# MCU.net
KiCad netlist of a schematic drawn in Altium Designer
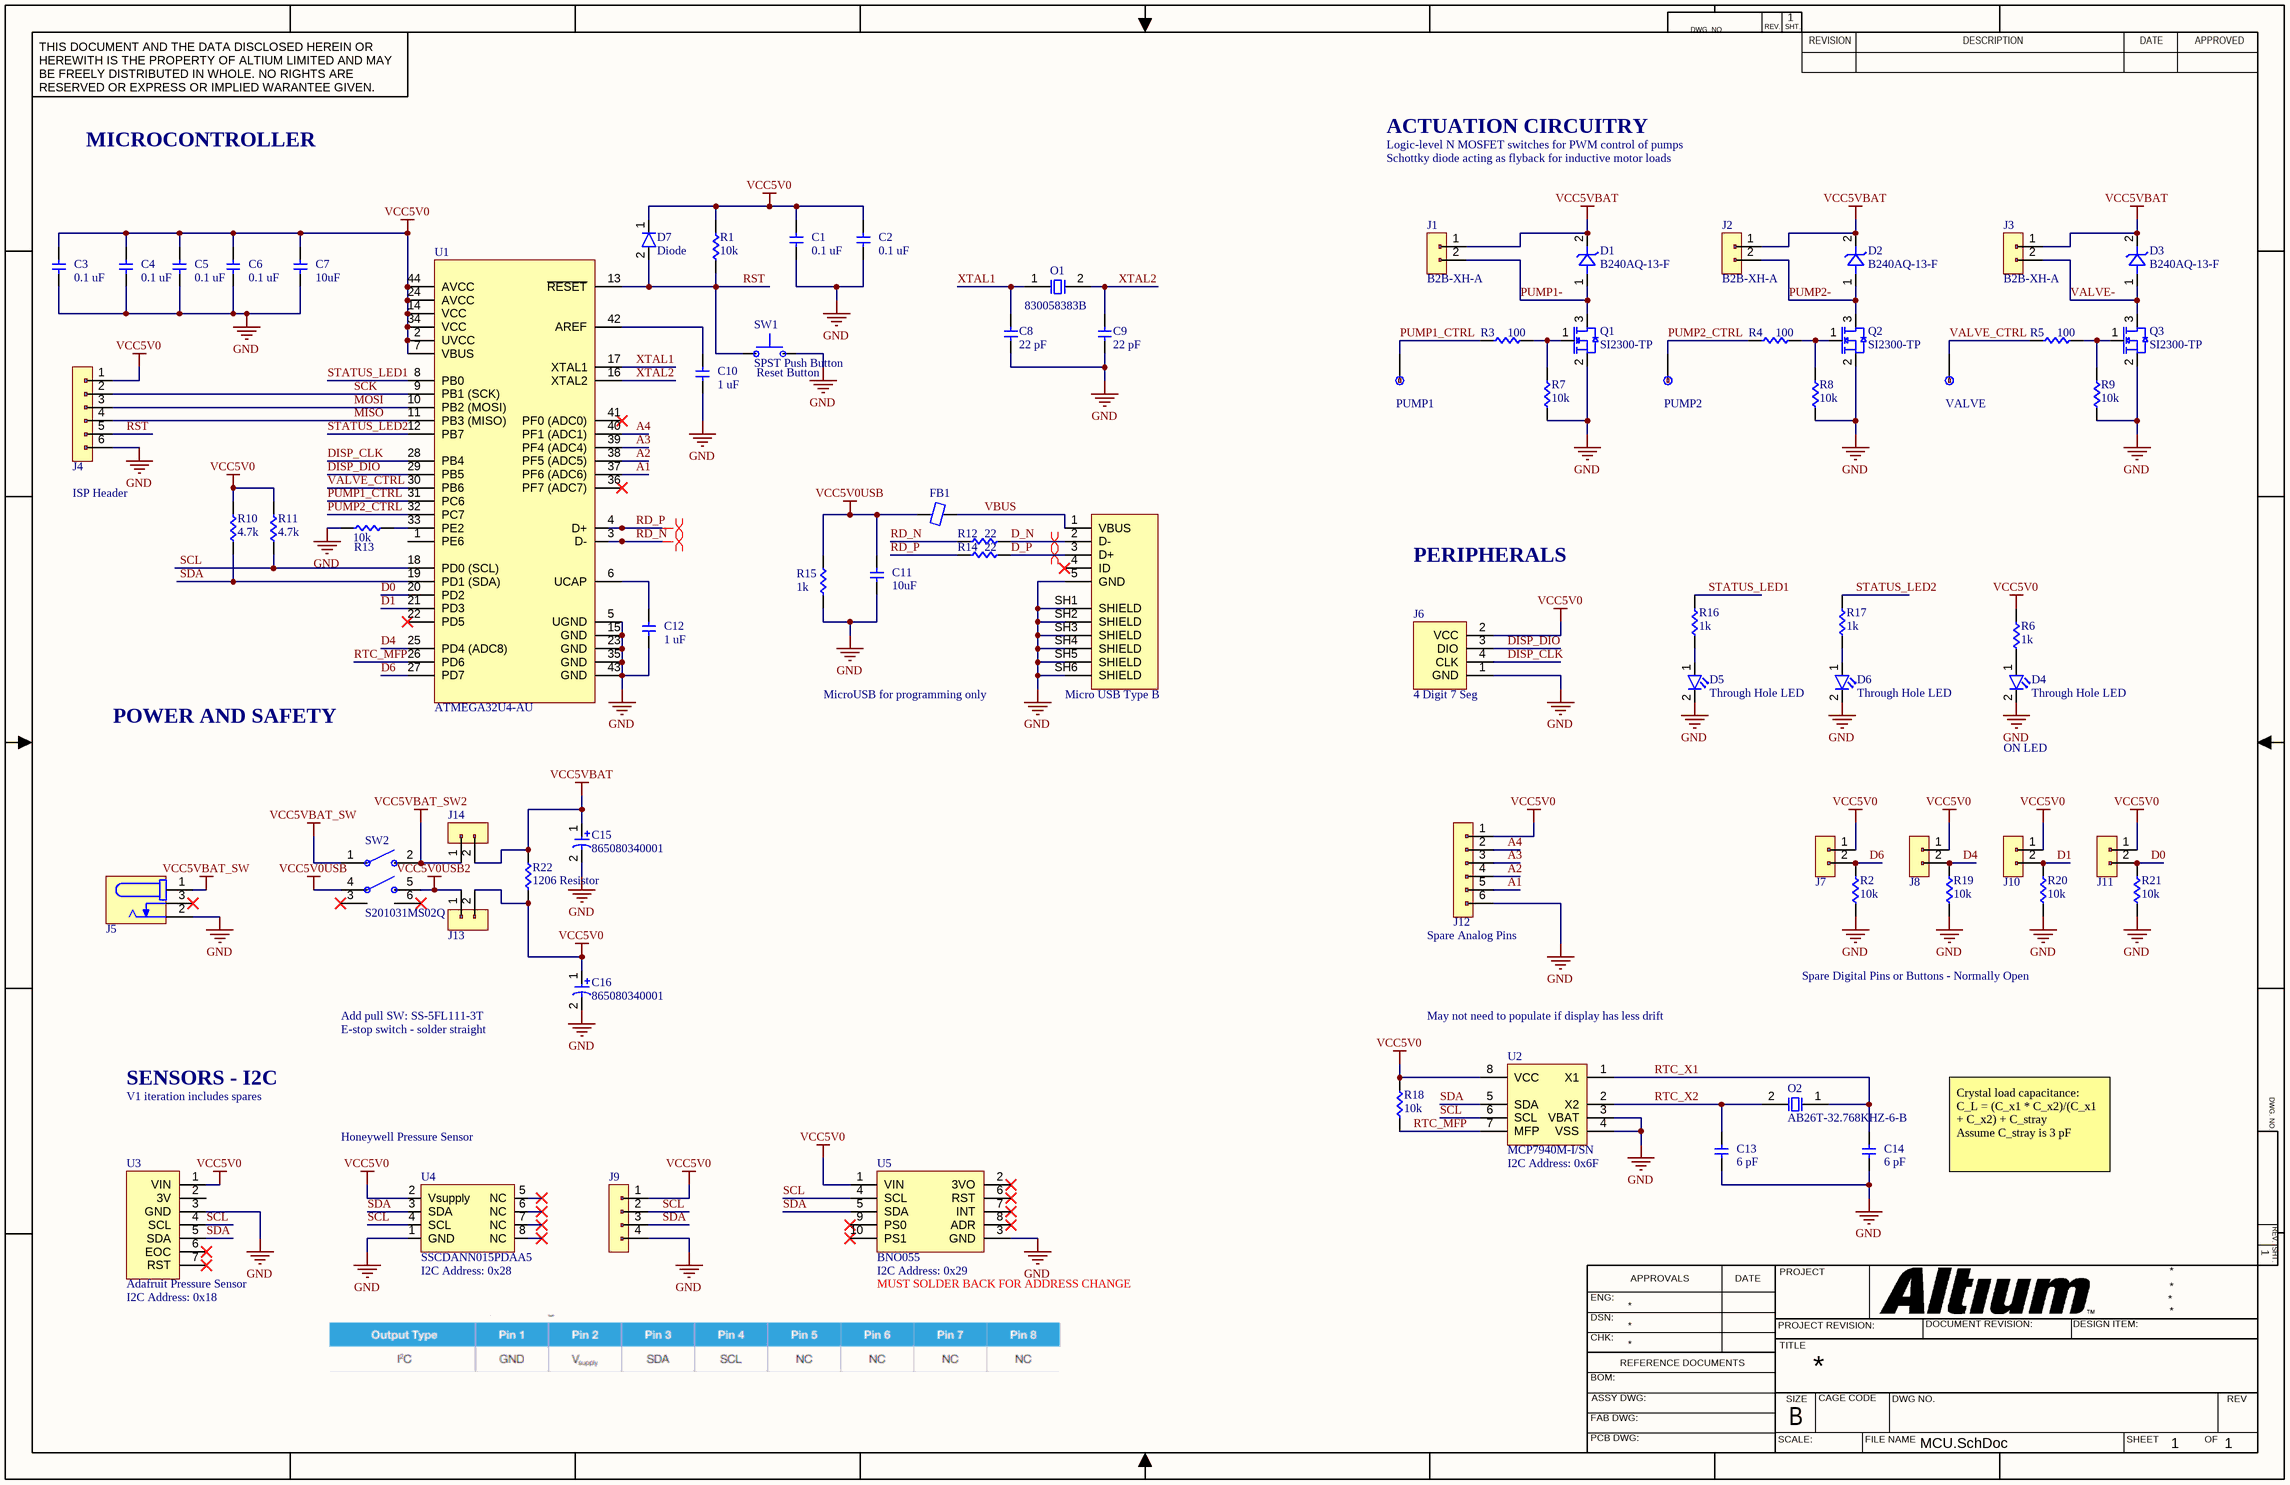
[diagram p0: MCU.SchDoc]

(export (version "E")
  (design (tool "Eeschema 10.0.6"))
  (components
    (comp (ref "*")
      (value "Micro USB Type B")
      (footprint "10118194-0001LF")
      (description "10118194-0001LF")
      (fields (field (name "MANUFACTURER") "Molex") (field (name "MANUFACTURER PART NUMBER") "105164-0001"))
      (libsource (lib "TourniquetPCBSch") (part "Micro USB Type B"))
    )
    (comp (ref "C1")
      (value "0.1 uF")
      (footprint "0603_CAP")
      (description "16V 100nF X7R ±10% 0603 Multilayer Ceramic Capacitors MLCC - SMD/SMT ROHS")
      (fields
        (field (name "MANUFACTURER") "Yageo Group")
        (field (name "MANUFACTURER PART NUMBER") "CC0603KRX7R7BB104")
      )
      (libsource (lib "TourniquetPCBSch") (part "CAPACITOR"))
    )
    (comp (ref "C2")
      (value "0.1 uF")
      (footprint "0603_CAP")
      (description "16V 100nF X7R ±10% 0603 Multilayer Ceramic Capacitors MLCC - SMD/SMT ROHS")
      (fields
        (field (name "MANUFACTURER") "Yageo Group")
        (field (name "MANUFACTURER PART NUMBER") "CC0603KRX7R7BB104")
      )
      (libsource (lib "TourniquetPCBSch") (part "CAPACITOR"))
    )
    (comp (ref "C3")
      (value "0.1 uF")
      (footprint "0603_CAP")
      (description "16V 100nF X7R ±10% 0603 Multilayer Ceramic Capacitors MLCC - SMD/SMT ROHS")
      (fields
        (field (name "MANUFACTURER") "Yageo Group")
        (field (name "MANUFACTURER PART NUMBER") "CC0603KRX7R7BB104")
      )
      (libsource (lib "TourniquetPCBSch") (part "CAPACITOR"))
    )
    (comp (ref "C4")
      (value "0.1 uF")
      (footprint "0603_CAP")
      (description "16V 100nF X7R ±10% 0603 Multilayer Ceramic Capacitors MLCC - SMD/SMT ROHS")
      (fields
        (field (name "MANUFACTURER") "Yageo Group")
        (field (name "MANUFACTURER PART NUMBER") "CC0603KRX7R7BB104")
      )
      (libsource (lib "TourniquetPCBSch") (part "CAPACITOR"))
    )
    (comp (ref "C5")
      (value "0.1 uF")
      (footprint "0603_CAP")
      (description "16V 100nF X7R ±10% 0603 Multilayer Ceramic Capacitors MLCC - SMD/SMT ROHS")
      (fields
        (field (name "MANUFACTURER") "Yageo Group")
        (field (name "MANUFACTURER PART NUMBER") "CC0603KRX7R7BB104")
      )
      (libsource (lib "TourniquetPCBSch") (part "CAPACITOR"))
    )
    (comp (ref "C6")
      (value "0.1 uF")
      (footprint "0603_CAP")
      (description "16V 100nF X7R ±10% 0603 Multilayer Ceramic Capacitors MLCC - SMD/SMT ROHS")
      (fields
        (field (name "MANUFACTURER") "Yageo Group")
        (field (name "MANUFACTURER PART NUMBER") "CC0603KRX7R7BB104")
      )
      (libsource (lib "TourniquetPCBSch") (part "CAPACITOR"))
    )
    (comp (ref "C7")
      (value "10uF")
      (footprint "0603_CAP")
      (description "16V 100nF X7R ±10% 0603 Multilayer Ceramic Capacitors MLCC - SMD/SMT ROHS")
      (fields
        (field (name "MANUFACTURER") "Yageo Group")
        (field (name "MANUFACTURER PART NUMBER") "CC0603KRX7R7BB104")
      )
      (libsource (lib "TourniquetPCBSch") (part "CAPACITOR"))
    )
    (comp (ref "C8")
      (value "22 pF")
      (footprint "0603_CAP")
      (description "16V 100nF X7R ±10% 0603 Multilayer Ceramic Capacitors MLCC - SMD/SMT ROHS")
      (fields
        (field (name "MANUFACTURER") "Yageo Group")
        (field (name "MANUFACTURER PART NUMBER") "CC0603KRX7R7BB104")
      )
      (libsource (lib "TourniquetPCBSch") (part "CAPACITOR"))
    )
    (comp (ref "C9")
      (value "22 pF")
      (footprint "0603_CAP")
      (description "16V 100nF X7R ±10% 0603 Multilayer Ceramic Capacitors MLCC - SMD/SMT ROHS")
      (fields
        (field (name "MANUFACTURER") "Yageo Group")
        (field (name "MANUFACTURER PART NUMBER") "CC0603KRX7R7BB104")
      )
      (libsource (lib "TourniquetPCBSch") (part "CAPACITOR"))
    )
    (comp (ref "C10")
      (value "1 uF")
      (footprint "0603_CAP")
      (description "16V 100nF X7R ±10% 0603 Multilayer Ceramic Capacitors MLCC - SMD/SMT ROHS")
      (fields
        (field (name "MANUFACTURER") "Yageo Group")
        (field (name "MANUFACTURER PART NUMBER") "CC0603KRX7R7BB104")
      )
      (libsource (lib "TourniquetPCBSch") (part "CAPACITOR"))
    )
    (comp (ref "C11")
      (value "10uF")
      (footprint "0603_CAP")
      (description "16V 100nF X7R ±10% 0603 Multilayer Ceramic Capacitors MLCC - SMD/SMT ROHS")
      (fields
        (field (name "MANUFACTURER") "Yageo Group")
        (field (name "MANUFACTURER PART NUMBER") "CC0603KRX7R7BB104")
      )
      (libsource (lib "TourniquetPCBSch") (part "CAPACITOR"))
    )
    (comp (ref "C12")
      (value "1 uF")
      (footprint "0603_CAP")
      (description "16V 100nF X7R ±10% 0603 Multilayer Ceramic Capacitors MLCC - SMD/SMT ROHS")
      (fields
        (field (name "MANUFACTURER") "Yageo Group")
        (field (name "MANUFACTURER PART NUMBER") "CC0603KRX7R7BB104")
      )
      (libsource (lib "TourniquetPCBSch") (part "CAPACITOR"))
    )
    (comp (ref "C13")
      (value "6 pF")
      (footprint "0603_CAP")
      (description "16V 100nF X7R ±10% 0603 Multilayer Ceramic Capacitors MLCC - SMD/SMT ROHS")
      (fields
        (field (name "MANUFACTURER") "Yageo Group")
        (field (name "MANUFACTURER PART NUMBER") "CC0603KRX7R7BB104")
      )
      (libsource (lib "TourniquetPCBSch") (part "CAPACITOR"))
    )
    (comp (ref "C14")
      (value "6 pF")
      (footprint "0603_CAP")
      (description "16V 100nF X7R ±10% 0603 Multilayer Ceramic Capacitors MLCC - SMD/SMT ROHS")
      (fields
        (field (name "MANUFACTURER") "Yageo Group")
        (field (name "MANUFACTURER PART NUMBER") "CC0603KRX7R7BB104")
      )
      (libsource (lib "TourniquetPCBSch") (part "CAPACITOR"))
    )
    (comp (ref "C15")
      (value "865080340001")
      (footprint "865080340001")
      (description "10 µF 16 V Aluminum Electrolytic Capacitors Radial, Can - SMD 2000 Hrs @ 105°C")
      (fields
        (field (name "MANUFACTURER") "Wurth")
        (field (name "MANUFACTURER PART NUMBER") "0878310641")
        (field (name "REVIEWED") "No")
      )
      (libsource (lib "TourniquetPCBSch") (part "CAP_POLARIZED"))
    )
    (comp (ref "C16")
      (value "865080340001")
      (footprint "865080340001")
      (description "10 µF 16 V Aluminum Electrolytic Capacitors Radial, Can - SMD 2000 Hrs @ 105°C")
      (fields
        (field (name "MANUFACTURER") "Wurth")
        (field (name "MANUFACTURER PART NUMBER") "0878310641")
        (field (name "REVIEWED") "No")
      )
      (libsource (lib "TourniquetPCBSch") (part "CAP_POLARIZED"))
    )
    (comp (ref "D1")
      (value "B240AQ-13-F")
      (footprint "SMA")
      (fields (field (name "MANUFACTURER") "Diodes Incorporated") (field (name "REVIEWED") "No"))
      (libsource (lib "TourniquetPCBSch") (part "SCHOTTKY"))
    )
    (comp (ref "D2")
      (value "B240AQ-13-F")
      (footprint "SMA")
      (fields (field (name "MANUFACTURER") "Diodes Incorporated") (field (name "REVIEWED") "No"))
      (libsource (lib "TourniquetPCBSch") (part "SCHOTTKY"))
    )
    (comp (ref "D3")
      (value "B240AQ-13-F")
      (footprint "SMA")
      (fields (field (name "MANUFACTURER") "Diodes Incorporated") (field (name "REVIEWED") "No"))
      (libsource (lib "TourniquetPCBSch") (part "SCHOTTKY"))
    )
    (comp (ref "D4")
      (value "Through Hole LED")
      (footprint "RED LED")
      (description "Red 645nm LED Indication - Discrete 2.1V Radial")
      (fields
        (field (name "MANUFACTURER") "Wurth Elektronik")
        (field (name "MANUFACTURER PART NUMBER") "151051RS11000")
      )
      (libsource (lib "TourniquetPCBSch") (part "LED RED DIFFUSED 5MM ROUND T/H"))
    )
    (comp (ref "D5")
      (value "Through Hole LED")
      (footprint "RED LED")
      (description "Red 645nm LED Indication - Discrete 2.1V Radial")
      (fields
        (field (name "MANUFACTURER") "Wurth Elektronik")
        (field (name "MANUFACTURER PART NUMBER") "151051RS11000")
      )
      (libsource (lib "TourniquetPCBSch") (part "LED RED DIFFUSED 5MM ROUND T/H"))
    )
    (comp (ref "D6")
      (value "Through Hole LED")
      (footprint "RED LED")
      (description "Red 645nm LED Indication - Discrete 2.1V Radial")
      (fields
        (field (name "MANUFACTURER") "Wurth Elektronik")
        (field (name "MANUFACTURER PART NUMBER") "151051RS11000")
      )
      (libsource (lib "TourniquetPCBSch") (part "LED RED DIFFUSED 5MM ROUND T/H"))
    )
    (comp (ref "D7")
      (value "Diode")
      (footprint "Diode")
      (description "Diode 100 V 150mA Surface Mount SOD-123")
      (fields (field (name "MANUFACTURER") "onsemi") (field (name "MANUFACTURER PART NUMBER") "1N4148WS"))
      (libsource (lib "TourniquetPCBSch") (part "Diode"))
    )
    (comp (ref "FB1")
      (value "Ferrite Bead 732-1591-2-ND")
      (footprint "Ferrite Bead")
      (description "30 Ohms @ 100 MHz 1 Signal Line Ferrite Bead 0603 (1608 Metric) 3A 40mOhm")
      (fields
        (field (name "MANUFACTURER") "KEMET")
        (field (name "MANUFACTURER PART NUMBER") "C0805F104K4RACTU")
      )
      (libsource (lib "TourniquetPCBSch") (part "Ferrite Bead 732-1591-2-ND"))
    )
    (comp (ref "J1")
      (value "B2B-XH-A")
      (footprint "B2B-XH")
      (description "Two Pin JST XH Header")
      (fields
        (field (name "MANUFACTURER") "Samtec")
        (field (name "MANUFACTURER PART NUMBER") "TSM-102-01-L-SV")
      )
      (libsource (lib "TourniquetPCBSch") (part "B2B-XH-A"))
    )
    (comp (ref "J2")
      (value "B2B-XH-A")
      (footprint "B2B-XH")
      (description "Two Pin JST XH Header")
      (fields
        (field (name "MANUFACTURER") "Samtec")
        (field (name "MANUFACTURER PART NUMBER") "TSM-102-01-L-SV")
      )
      (libsource (lib "TourniquetPCBSch") (part "B2B-XH-A"))
    )
    (comp (ref "J3")
      (value "B2B-XH-A")
      (footprint "B2B-XH")
      (description "Two Pin JST XH Header")
      (fields
        (field (name "MANUFACTURER") "Samtec")
        (field (name "MANUFACTURER PART NUMBER") "TSM-102-01-L-SV")
      )
      (libsource (lib "TourniquetPCBSch") (part "B2B-XH-A"))
    )
    (comp (ref "J4")
      (value "6PIN_HEADER")
      (footprint "6_pin_2.54mm")
      (fields
        (field (name "PART NUMBER") "0878310641")
        (field (name "MANUFACTURER") "Molex")
        (field (name "REVIEWED") "No")
      )
      (libsource (lib "TourniquetPCBSch") (part "6PIN_HEADER"))
    )
    (comp (ref "J5")
      (value "0878310641")
      (footprint "54-00166")
      (description "Barrel Jack")
      (fields (field (name "MANUFACTURER") "Molex") (field (name "REVIEWED") "No"))
      (libsource (lib "TourniquetPCBSch") (part "54-00166"))
    )
    (comp (ref "J6")
      (value "4 Digit 7 Seg")
      (footprint "B4B-XH")
      (fields
        (field (name "MANUFACTURER") "Sullins")
        (field (name "MANUFACTURER PART NUMBER") "NPTC041KFXC-RC")
      )
      (libsource (lib "TourniquetPCBSch") (part "4 Digit 7 Seg 1x4 Female Header"))
    )
    (comp (ref "J7")
      (value "0878310641")
      (footprint "2PIN_2.54mm")
      (description "2PIN")
      (fields (field (name "MANUFACTURER") "Molex") (field (name "REVIEWED") "No"))
      (libsource (lib "TourniquetPCBSch") (part "2PIN_HEADER"))
    )
    (comp (ref "J8")
      (value "0878310641")
      (footprint "2PIN_2.54mm")
      (description "2PIN")
      (fields (field (name "MANUFACTURER") "Molex") (field (name "REVIEWED") "No"))
      (libsource (lib "TourniquetPCBSch") (part "2PIN_HEADER"))
    )
    (comp (ref "J9")
      (value "4PIN_HEADER")
      (footprint "4PIN_2.54mm")
      (fields
        (field (name "PART NUMBER") "0878310641")
        (field (name "MANUFACTURER") "Molex")
        (field (name "REVIEWED") "No")
      )
      (libsource (lib "TourniquetPCBSch") (part "4PIN_HEADER"))
    )
    (comp (ref "J10")
      (value "0878310641")
      (footprint "2PIN_2.54mm")
      (description "2PIN")
      (fields (field (name "MANUFACTURER") "Molex") (field (name "REVIEWED") "No"))
      (libsource (lib "TourniquetPCBSch") (part "2PIN_HEADER"))
    )
    (comp (ref "J11")
      (value "0878310641")
      (footprint "2PIN_2.54mm")
      (description "2PIN")
      (fields (field (name "MANUFACTURER") "Molex") (field (name "REVIEWED") "No"))
      (libsource (lib "TourniquetPCBSch") (part "2PIN_HEADER"))
    )
    (comp (ref "J12")
      (value "6PIN_HEADER")
      (footprint "6_pin_2.54mm")
      (fields
        (field (name "PART NUMBER") "0878310641")
        (field (name "MANUFACTURER") "Molex")
        (field (name "REVIEWED") "No")
      )
      (libsource (lib "TourniquetPCBSch") (part "6PIN_HEADER"))
    )
    (comp (ref "J13")
      (value "0878310641")
      (footprint "2PIN_2.54mm")
      (description "2PIN")
      (fields (field (name "MANUFACTURER") "Molex") (field (name "REVIEWED") "No"))
      (libsource (lib "") (part "2PIN_HEADER_1"))
    )
    (comp (ref "J14")
      (value "0878310641")
      (footprint "2PIN_2.54mm")
      (description "2PIN")
      (fields (field (name "MANUFACTURER") "Molex") (field (name "REVIEWED") "No"))
      (libsource (lib "") (part "2PIN_HEADER_2"))
    )
    (comp (ref "O1")
      (value "830058383B")
      (footprint "830058383B")
      (description "16 MHz ±30ppm Crystal 20pF 40 Ohms HC-49/US")
      (fields
        (field (name "MANUFACTURER") "Epson")
        (field (name "MANUFACTURER PART NUMBER") "TSX-3225 16.0000MF18X-AC0")
      )
      (libsource (lib "TourniquetPCBSch") (part "830058383B"))
    )
    (comp (ref "O2")
      (value "AB26T-32.768KHZ-6-B")
      (footprint "XTAL_AB26T-32.768KHZ-6-B")
      (description "32.768 kHz ±20ppm Crystal 6pF 35 kOhms Cylindrical Can, Radial")
      (fields
        (field (name "MANUFACTURER") "Epson")
        (field (name "MANUFACTURER PART NUMBER") "TSX-3225 16.0000MF18X-AC0")
      )
      (libsource (lib "TourniquetPCBSch") (part "AB26T-32.768KHZ-6-B"))
    )
    (comp (ref "PUMP1")
      (value "1PIN_HEADER_TEST")
      (footprint "1PIN_2.54mm")
      (description "Test Point Hole")
      (fields
        (field (name "MANUFACTURER") "Molex")
        (field (name "MANUFACTURER PART NUMBER") "0878310641")
        (field (name "REVIEWED") "No")
      )
      (libsource (lib "TourniquetPCBSch") (part "1PIN_HEADER_TEST"))
    )
    (comp (ref "PUMP2")
      (value "1PIN_HEADER_TEST")
      (footprint "1PIN_2.54mm")
      (description "Test Point Hole")
      (fields
        (field (name "MANUFACTURER") "Molex")
        (field (name "MANUFACTURER PART NUMBER") "0878310641")
        (field (name "REVIEWED") "No")
      )
      (libsource (lib "TourniquetPCBSch") (part "1PIN_HEADER_TEST"))
    )
    (comp (ref "Q1")
      (value "SI2300-TP")
      (footprint "SOT23")
      (fields
        (field (name "MANUFACTURER") "MCC (Micro Commercial Components)")
        (field (name "REVIEWED") "No")
      )
      (libsource (lib "TourniquetPCBSch") (part "MOSFET_NCHANNEL"))
    )
    (comp (ref "Q2")
      (value "SI2300-TP")
      (footprint "SOT23")
      (fields
        (field (name "MANUFACTURER") "MCC (Micro Commercial Components)")
        (field (name "REVIEWED") "No")
      )
      (libsource (lib "TourniquetPCBSch") (part "MOSFET_NCHANNEL"))
    )
    (comp (ref "Q3")
      (value "SI2300-TP")
      (footprint "SOT23")
      (fields
        (field (name "MANUFACTURER") "MCC (Micro Commercial Components)")
        (field (name "REVIEWED") "No")
      )
      (libsource (lib "TourniquetPCBSch") (part "MOSFET_NCHANNEL"))
    )
    (comp (ref "R1")
      (value "10k")
      (footprint "0603_RES")
      (fields (field (name "TOLERANCE") "1%"))
      (libsource (lib "TourniquetPCBSch") (part "RESISTOR"))
    )
    (comp (ref "R2")
      (value "10k")
      (footprint "0603_RES")
      (fields (field (name "TOLERANCE") "1%"))
      (libsource (lib "TourniquetPCBSch") (part "RESISTOR"))
    )
    (comp (ref "R3")
      (value "100")
      (footprint "0603_RES")
      (fields (field (name "TOLERANCE") "1%"))
      (libsource (lib "TourniquetPCBSch") (part "RESISTOR"))
    )
    (comp (ref "R4")
      (value "100")
      (footprint "0603_RES")
      (fields (field (name "TOLERANCE") "1%"))
      (libsource (lib "TourniquetPCBSch") (part "RESISTOR"))
    )
    (comp (ref "R5")
      (value "100")
      (footprint "0603_RES")
      (fields (field (name "TOLERANCE") "1%"))
      (libsource (lib "TourniquetPCBSch") (part "RESISTOR"))
    )
    (comp (ref "R6")
      (value "1k")
      (footprint "0603_RES")
      (fields (field (name "TOLERANCE") "1%"))
      (libsource (lib "TourniquetPCBSch") (part "RESISTOR"))
    )
    (comp (ref "R7")
      (value "10k")
      (footprint "0603_RES")
      (fields (field (name "TOLERANCE") "1%"))
      (libsource (lib "TourniquetPCBSch") (part "RESISTOR"))
    )
    (comp (ref "R8")
      (value "10k")
      (footprint "0603_RES")
      (fields (field (name "TOLERANCE") "1%"))
      (libsource (lib "TourniquetPCBSch") (part "RESISTOR"))
    )
    (comp (ref "R9")
      (value "10k")
      (footprint "0603_RES")
      (fields (field (name "TOLERANCE") "1%"))
      (libsource (lib "TourniquetPCBSch") (part "RESISTOR"))
    )
    (comp (ref "R10")
      (value "4.7k")
      (footprint "0603_RES")
      (fields (field (name "TOLERANCE") "1%"))
      (libsource (lib "TourniquetPCBSch") (part "RESISTOR"))
    )
    (comp (ref "R11")
      (value "4.7k")
      (footprint "0603_RES")
      (fields (field (name "TOLERANCE") "1%"))
      (libsource (lib "TourniquetPCBSch") (part "RESISTOR"))
    )
    (comp (ref "R12")
      (value "22")
      (footprint "0603_RES")
      (fields (field (name "TOLERANCE") "1%"))
      (libsource (lib "TourniquetPCBSch") (part "RESISTOR"))
    )
    (comp (ref "R13")
      (value "10k")
      (footprint "0603_RES")
      (fields (field (name "TOLERANCE") "1%"))
      (libsource (lib "TourniquetPCBSch") (part "RESISTOR"))
    )
    (comp (ref "R14")
      (value "22")
      (footprint "0603_RES")
      (fields (field (name "TOLERANCE") "1%"))
      (libsource (lib "TourniquetPCBSch") (part "RESISTOR"))
    )
    (comp (ref "R15")
      (value "1k")
      (footprint "0603_RES")
      (fields (field (name "TOLERANCE") "1%"))
      (libsource (lib "TourniquetPCBSch") (part "RESISTOR"))
    )
    (comp (ref "R16")
      (value "1k")
      (footprint "0603_RES")
      (fields (field (name "TOLERANCE") "1%"))
      (libsource (lib "TourniquetPCBSch") (part "RESISTOR"))
    )
    (comp (ref "R17")
      (value "1k")
      (footprint "0603_RES")
      (fields (field (name "TOLERANCE") "1%"))
      (libsource (lib "TourniquetPCBSch") (part "RESISTOR"))
    )
    (comp (ref "R18")
      (value "10k")
      (footprint "0603_RES")
      (fields (field (name "TOLERANCE") "1%"))
      (libsource (lib "TourniquetPCBSch") (part "RESISTOR"))
    )
    (comp (ref "R19")
      (value "10k")
      (footprint "0603_RES")
      (fields (field (name "TOLERANCE") "1%"))
      (libsource (lib "TourniquetPCBSch") (part "RESISTOR"))
    )
    (comp (ref "R20")
      (value "10k")
      (footprint "0603_RES")
      (fields (field (name "TOLERANCE") "1%"))
      (libsource (lib "TourniquetPCBSch") (part "RESISTOR"))
    )
    (comp (ref "R21")
      (value "10k")
      (footprint "0603_RES")
      (fields (field (name "TOLERANCE") "1%"))
      (libsource (lib "TourniquetPCBSch") (part "RESISTOR"))
    )
    (comp (ref "R22")
      (value "1206 Resistor")
      (footprint "1206 Resistor")
      (libsource (lib "TourniquetPCBSch") (part "1206 Resistor"))
    )
    (comp (ref "SW1")
      (value "SPST Push Button")
      (footprint "Push Button")
      (description "Switch Tactile N.O. SPST Round Button Gull Wing 0.05A 12VDC 1.5N SMD Embossed T/R")
      (fields (field (name "MANUFACTURER") "Omron") (field (name "MANUFACTURER PART NUMBER") "B3U-1100PM"))
      (libsource (lib "TourniquetPCBSch") (part "SPST Push Button"))
    )
    (comp (ref "SW2")
      (value "S201031MS02Q")
      (footprint "DPST Sliding Switch")
      (libsource (lib "TourniquetPCBSch") (part "DPST Switch"))
    )
    (comp (ref "U1")
      (value "ATMEGA32U4-AU")
      (footprint "ATMEGA32U4-AU")
      (description "Microcontroller, Usb Controller 16/32K Of Isp Flash, TQFP44 Industrial, 8-BIT")
      (fields (field (name "MANUFACTURER") "Microchip"))
      (libsource (lib "TourniquetPCBSch") (part "ATMEGA32U4-AU"))
    )
    (comp (ref "U2")
      (value "MCP7940M-I/SN")
      (footprint "8SOIC")
      (description "RTC Clock")
      (fields
        (field (name "PART NUMBER") "0878310641")
        (field (name "MANUFACTURER") "Molex")
        (field (name "REVIEWED") "No")
      )
      (libsource (lib "TourniquetPCBSch") (part "MCP7940M"))
    )
    (comp (ref "U3")
      (value "Adafruit Pressure Sensor")
      (footprint "Adafruit Pressure Sensor")
      (description "Adafruit MPRLS Ported Pressure Sensor")
      (fields
        (field (name "MANUFACTURER") "Wurth Elektronik")
        (field (name "MANUFACTURER PART NUMBER") "61300711121")
      )
      (libsource (lib "TourniquetPCBSch") (part "Adafruit MPRLS Ported Pressure Sensor"))
    )
    (comp (ref "U4")
      (value "SSCDANN015PDAA5")
      (footprint "SSCDANN015PDAA5")
      (fields
        (field (name "MANUFACTURER") "Sullins")
        (field (name "MANUFACTURER PART NUMBER") "NPTC041KFXC-RC")
      )
      (libsource (lib "TourniquetPCBSch") (part "SSCDANN015PDAA5"))
    )
    (comp (ref "U5")
      (value "BNO055")
      (footprint "BNO055")
      (description "IMU")
      (fields
        (field (name "MANUFACTURER") "Adafruit")
        (field (name "MANUFACTURER PART NUMBER") "0878310641")
        (field (name "REVIEWED") "No")
      )
      (libsource (lib "TourniquetPCBSch") (part "BNO055"))
    )
    (comp (ref "VALVE")
      (value "1PIN_HEADER_TEST")
      (footprint "1PIN_2.54mm")
      (description "Test Point Hole")
      (fields
        (field (name "MANUFACTURER") "Molex")
        (field (name "MANUFACTURER PART NUMBER") "0878310641")
        (field (name "REVIEWED") "No")
      )
      (libsource (lib "TourniquetPCBSch") (part "1PIN_HEADER_TEST"))
    )
  )
  (nets
    (net (code "1") (name "/A1") (class "Default")
      (node (ref "J12") (pin "5") (pintype "passive"))
      (node (ref "U1") (pin "37") (pinfunction "PF6_(ADC6)_37") (pintype "passive"))
    )
    (net (code "2") (name "/A2") (class "Default")
      (node (ref "J12") (pin "4") (pintype "passive"))
      (node (ref "U1") (pin "38") (pinfunction "PF5_(ADC5)_38") (pintype "passive"))
    )
    (net (code "3") (name "/A3") (class "Default")
      (node (ref "J12") (pin "3") (pintype "passive"))
      (node (ref "U1") (pin "39") (pinfunction "PF4_(ADC4)_39") (pintype "passive"))
    )
    (net (code "4") (name "/A4") (class "Default")
      (node (ref "J12") (pin "2") (pintype "passive"))
      (node (ref "U1") (pin "40") (pinfunction "PF1_(ADC1)_40") (pintype "passive"))
    )
    (net (code "5") (name "/D0") (class "Default")
      (node (ref "J11") (pin "2") (pintype "passive"))
      (node (ref "R21") (pin "1") (pinfunction "1_1") (pintype "passive"))
      (node (ref "U1") (pin "20") (pinfunction "PD2_20") (pintype "passive"))
    )
    (net (code "6") (name "/D1") (class "Default")
      (node (ref "J10") (pin "2") (pintype "passive"))
      (node (ref "R20") (pin "1") (pinfunction "1_1") (pintype "passive"))
      (node (ref "U1") (pin "21") (pinfunction "PD3_21") (pintype "passive"))
    )
    (net (code "7") (name "/D4") (class "Default")
      (node (ref "J8") (pin "2") (pintype "passive"))
      (node (ref "R19") (pin "1") (pinfunction "1_1") (pintype "passive"))
      (node (ref "U1") (pin "25") (pinfunction "PD4_(ADC8)_25") (pintype "passive"))
    )
    (net (code "8") (name "/D6") (class "Default")
      (node (ref "J7") (pin "2") (pintype "passive"))
      (node (ref "R2") (pin "1") (pinfunction "1_1") (pintype "passive"))
      (node (ref "U1") (pin "27") (pinfunction "PD7_27") (pintype "passive"))
    )
    (net (code "9") (name "/DISP_CLK") (class "Default")
      (node (ref "J6") (pin "4") (pinfunction "CLK_4") (pintype "passive"))
      (node (ref "U1") (pin "28") (pinfunction "PB4_28") (pintype "passive"))
    )
    (net (code "10") (name "/DISP_DIO") (class "Default")
      (node (ref "J6") (pin "3") (pinfunction "DIO_3") (pintype "passive"))
      (node (ref "U1") (pin "29") (pinfunction "PB5_29") (pintype "passive"))
    )
    (net (code "11") (name "/D_N") (class "Default")
      (node (ref "*") (pin "2") (pinfunction "D-_2") (pintype "passive"))
      (node (ref "R12") (pin "2") (pinfunction "2_2") (pintype "passive"))
    )
    (net (code "12") (name "/D_P") (class "Default")
      (node (ref "*") (pin "3") (pinfunction "D+_3") (pintype "passive"))
      (node (ref "R14") (pin "2") (pinfunction "2_2") (pintype "passive"))
    )
    (net (code "13") (name "/MISO") (class "Default")
      (node (ref "J4") (pin "4") (pintype "passive"))
      (node (ref "U1") (pin "11") (pinfunction "PB3_(MISO)_11") (pintype "passive"))
    )
    (net (code "14") (name "/MOSI") (class "Default")
      (node (ref "J4") (pin "3") (pintype "passive"))
      (node (ref "U1") (pin "10") (pinfunction "PB2_(MOSI)_10") (pintype "passive"))
    )
    (net (code "15") (name "/PUMP1-") (class "Default")
      (node (ref "D1") (pin "1") (pinfunction "A_1") (pintype "passive"))
      (node (ref "J1") (pin "2") (pintype "passive"))
      (node (ref "Q1") (pin "3") (pinfunction "D_3") (pintype "passive"))
    )
    (net (code "16") (name "/PUMP1_CTRL") (class "Default")
      (node (ref "PUMP1") (pin "1") (pintype "passive"))
      (node (ref "R3") (pin "1") (pinfunction "1_1") (pintype "passive"))
      (node (ref "U1") (pin "31") (pinfunction "PC6_31") (pintype "passive"))
    )
    (net (code "17") (name "/PUMP2-") (class "Default")
      (node (ref "D2") (pin "1") (pinfunction "A_1") (pintype "passive"))
      (node (ref "J2") (pin "2") (pintype "passive"))
      (node (ref "Q2") (pin "3") (pinfunction "D_3") (pintype "passive"))
    )
    (net (code "18") (name "/PUMP2_CTRL") (class "Default")
      (node (ref "PUMP2") (pin "1") (pintype "passive"))
      (node (ref "R4") (pin "1") (pinfunction "1_1") (pintype "passive"))
      (node (ref "U1") (pin "32") (pinfunction "PC7_32") (pintype "passive"))
    )
    (net (code "19") (name "/RD_N") (class "Default")
      (node (ref "R12") (pin "1") (pinfunction "1_1") (pintype "passive"))
      (node (ref "U1") (pin "3") (pinfunction "D-_3") (pintype "passive"))
    )
    (net (code "20") (name "/RD_P") (class "Default")
      (node (ref "R14") (pin "1") (pinfunction "1_1") (pintype "passive"))
      (node (ref "U1") (pin "4") (pinfunction "D+_4") (pintype "passive"))
    )
    (net (code "21") (name "/RST") (class "Default")
      (node (ref "D7") (pin "2") (pinfunction "Anode_2") (pintype "passive"))
      (node (ref "J4") (pin "5") (pintype "passive"))
      (node (ref "R1") (pin "2") (pinfunction "2_2") (pintype "passive"))
      (node (ref "SW1") (pin "1") (pintype "passive"))
      (node (ref "U1") (pin "13") (pinfunction "~{RESET}_13") (pintype "passive"))
    )
    (net (code "22") (name "/RTC_MFP") (class "Default")
      (node (ref "R18") (pin "1") (pinfunction "1_1") (pintype "passive"))
      (node (ref "U1") (pin "26") (pinfunction "PD6_26") (pintype "passive"))
      (node (ref "U2") (pin "7") (pinfunction "MFP_7") (pintype "passive"))
    )
    (net (code "23") (name "/RTC_X1") (class "Default")
      (node (ref "C14") (pin "1") (pinfunction "1_1") (pintype "passive"))
      (node (ref "O2") (pin "1") (pinfunction "XTAL1_1") (pintype "passive"))
      (node (ref "U2") (pin "1") (pinfunction "X1_1") (pintype "passive"))
    )
    (net (code "24") (name "/RTC_X2") (class "Default")
      (node (ref "C13") (pin "1") (pinfunction "1_1") (pintype "passive"))
      (node (ref "O2") (pin "2") (pinfunction "GND_2") (pintype "passive"))
      (node (ref "U2") (pin "2") (pinfunction "X2_2") (pintype "passive"))
    )
    (net (code "25") (name "/SCK") (class "Default")
      (node (ref "J4") (pin "2") (pintype "passive"))
      (node (ref "U1") (pin "9") (pinfunction "PB1_(SCK)_9") (pintype "passive"))
    )
    (net (code "26") (name "/SCL") (class "Default")
      (node (ref "J9") (pin "2") (pintype "passive"))
      (node (ref "R11") (pin "2") (pinfunction "2_2") (pintype "passive"))
      (node (ref "U1") (pin "18") (pinfunction "PD0_(SCL)_18") (pintype "passive"))
      (node (ref "U2") (pin "6") (pinfunction "SCL_6") (pintype "passive"))
      (node (ref "U3") (pin "4") (pinfunction "SCL_4") (pintype "passive"))
      (node (ref "U4") (pin "4") (pinfunction "SCL_4") (pintype "passive"))
      (node (ref "U5") (pin "4") (pinfunction "SCL_4") (pintype "passive"))
    )
    (net (code "27") (name "/SDA") (class "Default")
      (node (ref "J9") (pin "3") (pintype "passive"))
      (node (ref "R10") (pin "2") (pinfunction "2_2") (pintype "passive"))
      (node (ref "U1") (pin "19") (pinfunction "PD1_(SDA)_19") (pintype "passive"))
      (node (ref "U2") (pin "5") (pinfunction "SDA_5") (pintype "passive"))
      (node (ref "U3") (pin "5") (pinfunction "SDA_5") (pintype "passive"))
      (node (ref "U4") (pin "3") (pinfunction "SDA_3") (pintype "passive"))
      (node (ref "U5") (pin "5") (pinfunction "SDA_5") (pintype "passive"))
    )
    (net (code "28") (name "/STATUS_LED1") (class "Default")
      (node (ref "R16") (pin "1") (pinfunction "1_1") (pintype "passive"))
      (node (ref "U1") (pin "8") (pinfunction "PB0_8") (pintype "passive"))
    )
    (net (code "29") (name "/STATUS_LED2") (class "Default")
      (node (ref "R17") (pin "1") (pinfunction "1_1") (pintype "passive"))
      (node (ref "U1") (pin "12") (pinfunction "PB7_12") (pintype "passive"))
    )
    (net (code "30") (name "/VALVE-") (class "Default")
      (node (ref "D3") (pin "1") (pinfunction "A_1") (pintype "passive"))
      (node (ref "J3") (pin "2") (pintype "passive"))
      (node (ref "Q3") (pin "3") (pinfunction "D_3") (pintype "passive"))
    )
    (net (code "31") (name "/VALVE_CTRL") (class "Default")
      (node (ref "R5") (pin "1") (pinfunction "1_1") (pintype "passive"))
      (node (ref "U1") (pin "30") (pinfunction "PB6_30") (pintype "passive"))
      (node (ref "VALVE") (pin "1") (pintype "passive"))
    )
    (net (code "32") (name "/VBUS") (class "Default")
      (node (ref "*") (pin "1") (pinfunction "VBUS_1") (pintype "passive"))
      (node (ref "FB1") (pin "2") (pinfunction "2_2") (pintype "passive"))
    )
    (net (code "33") (name "/XTAL1") (class "Default")
      (node (ref "C8") (pin "2") (pinfunction "2_2") (pintype "passive"))
      (node (ref "O1") (pin "1") (pinfunction "XTAL1_1") (pintype "passive"))
      (node (ref "U1") (pin "17") (pinfunction "XTAL1_17") (pintype "passive"))
    )
    (net (code "34") (name "/XTAL2") (class "Default")
      (node (ref "C9") (pin "2") (pinfunction "2_2") (pintype "passive"))
      (node (ref "O1") (pin "2") (pinfunction "GND_2") (pintype "passive"))
      (node (ref "U1") (pin "16") (pinfunction "XTAL2_16") (pintype "passive"))
    )
    (net (code "35") (name "GND") (class "Default")
      (node (ref "*") (pin "5") (pinfunction "GND_5") (pintype "passive"))
      (node (ref "*") (pin "SH1") (pinfunction "SHIELD_SH1") (pintype "passive"))
      (node (ref "*") (pin "SH2") (pinfunction "SHIELD_SH2") (pintype "passive"))
      (node (ref "*") (pin "SH3") (pinfunction "SHIELD_SH3") (pintype "passive"))
      (node (ref "*") (pin "SH4") (pinfunction "SHIELD_SH4") (pintype "passive"))
      (node (ref "*") (pin "SH5") (pinfunction "SHIELD_SH5") (pintype "passive"))
      (node (ref "*") (pin "SH6") (pinfunction "SHIELD_SH6") (pintype "passive"))
      (node (ref "C1") (pin "2") (pinfunction "2_2") (pintype "passive"))
      (node (ref "C10") (pin "2") (pinfunction "2_2") (pintype "passive"))
      (node (ref "C11") (pin "2") (pinfunction "2_2") (pintype "passive"))
      (node (ref "C12") (pin "2") (pinfunction "2_2") (pintype "passive"))
      (node (ref "C13") (pin "2") (pinfunction "2_2") (pintype "passive"))
      (node (ref "C14") (pin "2") (pinfunction "2_2") (pintype "passive"))
      (node (ref "C15") (pin "2") (pinfunction "NEG_2") (pintype "passive"))
      (node (ref "C16") (pin "2") (pinfunction "NEG_2") (pintype "passive"))
      (node (ref "C2") (pin "2") (pinfunction "2_2") (pintype "passive"))
      (node (ref "C3") (pin "2") (pinfunction "2_2") (pintype "passive"))
      (node (ref "C4") (pin "2") (pinfunction "2_2") (pintype "passive"))
      (node (ref "C5") (pin "2") (pinfunction "2_2") (pintype "passive"))
      (node (ref "C6") (pin "2") (pinfunction "2_2") (pintype "passive"))
      (node (ref "C7") (pin "2") (pinfunction "2_2") (pintype "passive"))
      (node (ref "C8") (pin "1") (pinfunction "1_1") (pintype "passive"))
      (node (ref "C9") (pin "1") (pinfunction "1_1") (pintype "passive"))
      (node (ref "D4") (pin "2") (pinfunction "Cathode_2") (pintype "passive"))
      (node (ref "D5") (pin "2") (pinfunction "Cathode_2") (pintype "passive"))
      (node (ref "D6") (pin "2") (pinfunction "Cathode_2") (pintype "passive"))
      (node (ref "J12") (pin "6") (pintype "passive"))
      (node (ref "J4") (pin "6") (pintype "passive"))
      (node (ref "J5") (pin "2") (pinfunction "B_2") (pintype "passive"))
      (node (ref "J6") (pin "1") (pinfunction "GND_1") (pintype "passive"))
      (node (ref "J9") (pin "4") (pintype "passive"))
      (node (ref "Q1") (pin "2") (pinfunction "S_2") (pintype "passive"))
      (node (ref "Q2") (pin "2") (pinfunction "S_2") (pintype "passive"))
      (node (ref "Q3") (pin "2") (pinfunction "S_2") (pintype "passive"))
      (node (ref "R13") (pin "1") (pinfunction "1_1") (pintype "passive"))
      (node (ref "R15") (pin "1") (pinfunction "1_1") (pintype "passive"))
      (node (ref "R19") (pin "2") (pinfunction "2_2") (pintype "passive"))
      (node (ref "R2") (pin "2") (pinfunction "2_2") (pintype "passive"))
      (node (ref "R20") (pin "2") (pinfunction "2_2") (pintype "passive"))
      (node (ref "R21") (pin "2") (pinfunction "2_2") (pintype "passive"))
      (node (ref "R7") (pin "2") (pinfunction "2_2") (pintype "passive"))
      (node (ref "R8") (pin "2") (pinfunction "2_2") (pintype "passive"))
      (node (ref "R9") (pin "2") (pinfunction "2_2") (pintype "passive"))
      (node (ref "SW1") (pin "2") (pintype "passive"))
      (node (ref "U1") (pin "15") (pinfunction "GND_15") (pintype "passive"))
      (node (ref "U1") (pin "23") (pinfunction "GND_23") (pintype "passive"))
      (node (ref "U1") (pin "35") (pinfunction "GND_35") (pintype "passive"))
      (node (ref "U1") (pin "43") (pinfunction "GND_43") (pintype "passive"))
      (node (ref "U1") (pin "5") (pinfunction "UGND_5") (pintype "passive"))
      (node (ref "U2") (pin "3") (pinfunction "VBAT_3") (pintype "passive"))
      (node (ref "U2") (pin "4") (pinfunction "VSS_4") (pintype "passive"))
      (node (ref "U3") (pin "3") (pinfunction "GND_3") (pintype "passive"))
      (node (ref "U4") (pin "1") (pinfunction "GND_1") (pintype "passive"))
      (node (ref "U5") (pin "3") (pinfunction "GND_3") (pintype "power_in"))
    )
    (net (code "36") (name "Net-(D4-Anode)") (class "Default")
      (node (ref "D4") (pin "1") (pinfunction "Anode_1") (pintype "passive"))
      (node (ref "R6") (pin "2") (pinfunction "2_2") (pintype "passive"))
    )
    (net (code "37") (name "Net-(D5-Anode)") (class "Default")
      (node (ref "D5") (pin "1") (pinfunction "Anode_1") (pintype "passive"))
      (node (ref "R16") (pin "2") (pinfunction "2_2") (pintype "passive"))
    )
    (net (code "38") (name "Net-(D6-Anode)") (class "Default")
      (node (ref "D6") (pin "1") (pinfunction "Anode_1") (pintype "passive"))
      (node (ref "R17") (pin "2") (pinfunction "2_2") (pintype "passive"))
    )
    (net (code "39") (name "Net-(Q1-G)") (class "Default")
      (node (ref "Q1") (pin "1") (pinfunction "G_1") (pintype "passive"))
      (node (ref "R3") (pin "2") (pinfunction "2_2") (pintype "passive"))
      (node (ref "R7") (pin "1") (pinfunction "1_1") (pintype "passive"))
    )
    (net (code "40") (name "Net-(Q2-G)") (class "Default")
      (node (ref "Q2") (pin "1") (pinfunction "G_1") (pintype "passive"))
      (node (ref "R4") (pin "2") (pinfunction "2_2") (pintype "passive"))
      (node (ref "R8") (pin "1") (pinfunction "1_1") (pintype "passive"))
    )
    (net (code "41") (name "Net-(Q3-G)") (class "Default")
      (node (ref "Q3") (pin "1") (pinfunction "G_1") (pintype "passive"))
      (node (ref "R5") (pin "2") (pinfunction "2_2") (pintype "passive"))
      (node (ref "R9") (pin "1") (pinfunction "1_1") (pintype "passive"))
    )
    (net (code "42") (name "Net-(U1-AREF)") (class "Default")
      (node (ref "C10") (pin "1") (pinfunction "1_1") (pintype "passive"))
      (node (ref "U1") (pin "42") (pinfunction "AREF_42") (pintype "passive"))
    )
    (net (code "43") (name "Net-(U1-PE2)") (class "Default")
      (node (ref "R13") (pin "2") (pinfunction "2_2") (pintype "passive"))
      (node (ref "U1") (pin "33") (pinfunction "PE2_33") (pintype "passive"))
    )
    (net (code "44") (name "Net-(U1-UCAP)") (class "Default")
      (node (ref "C12") (pin "1") (pinfunction "1_1") (pintype "passive"))
      (node (ref "U1") (pin "6") (pinfunction "UCAP_6") (pintype "passive"))
    )
    (net (code "45") (name "VCC5V0") (class "Default")
      (node (ref "C1") (pin "1") (pinfunction "1_1") (pintype "passive"))
      (node (ref "C16") (pin "1") (pinfunction "POS_1") (pintype "passive"))
      (node (ref "C2") (pin "1") (pinfunction "1_1") (pintype "passive"))
      (node (ref "C3") (pin "1") (pinfunction "1_1") (pintype "passive"))
      (node (ref "C4") (pin "1") (pinfunction "1_1") (pintype "passive"))
      (node (ref "C5") (pin "1") (pinfunction "1_1") (pintype "passive"))
      (node (ref "C6") (pin "1") (pinfunction "1_1") (pintype "passive"))
      (node (ref "C7") (pin "1") (pinfunction "1_1") (pintype "passive"))
      (node (ref "D7") (pin "1") (pinfunction "Cathode_1") (pintype "passive"))
      (node (ref "J10") (pin "1") (pinfunction "SCL_1") (pintype "passive"))
      (node (ref "J11") (pin "1") (pinfunction "SCL_1") (pintype "passive"))
      (node (ref "J12") (pin "1") (pinfunction "SCL_1") (pintype "passive"))
      (node (ref "J13") (pin "2") (pintype "passive"))
      (node (ref "J4") (pin "1") (pinfunction "SCL_1") (pintype "passive"))
      (node (ref "J6") (pin "2") (pinfunction "VCC_2") (pintype "passive"))
      (node (ref "J7") (pin "1") (pinfunction "SCL_1") (pintype "passive"))
      (node (ref "J8") (pin "1") (pinfunction "SCL_1") (pintype "passive"))
      (node (ref "J9") (pin "1") (pinfunction "SCL_1") (pintype "passive"))
      (node (ref "R1") (pin "1") (pinfunction "1_1") (pintype "passive"))
      (node (ref "R10") (pin "1") (pinfunction "1_1") (pintype "passive"))
      (node (ref "R11") (pin "1") (pinfunction "1_1") (pintype "passive"))
      (node (ref "R18") (pin "2") (pinfunction "2_2") (pintype "passive"))
      (node (ref "R22") (pin "1") (pinfunction "1_1") (pintype "passive"))
      (node (ref "R6") (pin "1") (pinfunction "1_1") (pintype "passive"))
      (node (ref "U1") (pin "14") (pinfunction "VCC_14") (pintype "passive"))
      (node (ref "U1") (pin "2") (pinfunction "UVCC_2") (pintype "passive"))
      (node (ref "U1") (pin "24") (pinfunction "AVCC_24") (pintype "passive"))
      (node (ref "U1") (pin "34") (pinfunction "VCC_34") (pintype "passive"))
      (node (ref "U1") (pin "44") (pinfunction "AVCC_44") (pintype "passive"))
      (node (ref "U1") (pin "7") (pinfunction "VBUS_7") (pintype "passive"))
      (node (ref "U2") (pin "8") (pinfunction "VCC_8") (pintype "power_in"))
      (node (ref "U3") (pin "1") (pinfunction "VIN_1") (pintype "passive"))
      (node (ref "U4") (pin "2") (pinfunction "Vsupply_2") (pintype "passive"))
      (node (ref "U5") (pin "1") (pinfunction "VIN_1") (pintype "power_in"))
    )
    (net (code "46") (name "VCC5V0USB") (class "Default")
      (node (ref "C11") (pin "1") (pinfunction "1_1") (pintype "passive"))
      (node (ref "FB1") (pin "1") (pinfunction "1_1") (pintype "passive"))
      (node (ref "R15") (pin "2") (pinfunction "2_2") (pintype "passive"))
      (node (ref "SW2") (pin "4") (pinfunction "NC2_4") (pintype "passive"))
    )
    (net (code "47") (name "VCC5V0USB2") (class "Default")
      (node (ref "J13") (pin "1") (pinfunction "SCL_1") (pintype "passive"))
      (node (ref "SW2") (pin "5") (pinfunction "COM2_5") (pintype "passive"))
    )
    (net (code "48") (name "VCC5VBAT") (class "Default")
      (node (ref "C15") (pin "1") (pinfunction "POS_1") (pintype "passive"))
      (node (ref "D1") (pin "2") (pinfunction "K_2") (pintype "passive"))
      (node (ref "D2") (pin "2") (pinfunction "K_2") (pintype "passive"))
      (node (ref "D3") (pin "2") (pinfunction "K_2") (pintype "passive"))
      (node (ref "J1") (pin "1") (pinfunction "SCL_1") (pintype "passive"))
      (node (ref "J14") (pin "2") (pinfunction "SCL_2") (pintype "passive"))
      (node (ref "J2") (pin "1") (pinfunction "SCL_1") (pintype "passive"))
      (node (ref "J3") (pin "1") (pinfunction "SCL_1") (pintype "passive"))
      (node (ref "R22") (pin "2") (pinfunction "2_2") (pintype "passive"))
    )
    (net (code "49") (name "VCC5VBAT_SW") (class "Default")
      (node (ref "J5") (pin "1") (pinfunction "A_1") (pintype "passive"))
      (node (ref "SW2") (pin "1") (pinfunction "NC1_1") (pintype "passive"))
    )
    (net (code "50") (name "VCC5VBAT_SW2") (class "Default")
      (node (ref "J14") (pin "1") (pintype "passive"))
      (node (ref "SW2") (pin "2") (pinfunction "COM1_2") (pintype "passive"))
    )
    (net (code "51") (name "unconnected-(*-ID-Pad4)") (class "Default")
      (node (ref "*") (pin "4") (pinfunction "ID_4") (pintype "passive+no_connect"))
    )
    (net (code "52") (name "unconnected-(J5-C-Pad3)") (class "Default")
      (node (ref "J5") (pin "3") (pinfunction "C_3") (pintype "passive+no_connect"))
    )
    (net (code "53") (name "unconnected-(SW2-NC2-Pad3)") (class "Default")
      (node (ref "SW2") (pin "3") (pinfunction "NC2_3") (pintype "passive+no_connect"))
    )
    (net (code "54") (name "unconnected-(SW2-NC2-Pad6)") (class "Default")
      (node (ref "SW2") (pin "6") (pinfunction "NC2_6") (pintype "passive+no_connect"))
    )
    (net (code "55") (name "unconnected-(U1-PD5-Pad22)") (class "Default")
      (node (ref "U1") (pin "22") (pinfunction "PD5_22") (pintype "passive+no_connect"))
    )
    (net (code "56") (name "unconnected-(U1-PE6-Pad1)") (class "Default")
      (node (ref "U1") (pin "1") (pinfunction "PE6_1") (pintype "passive"))
    )
    (net (code "57") (name "unconnected-(U1-PF0_(ADC0)-Pad41)") (class "Default")
      (node (ref "U1") (pin "41") (pinfunction "PF0_(ADC0)_41") (pintype "passive+no_connect"))
    )
    (net (code "58") (name "unconnected-(U1-PF7_(ADC7)-Pad36)") (class "Default")
      (node (ref "U1") (pin "36") (pinfunction "PF7_(ADC7)_36") (pintype "passive+no_connect"))
    )
    (net (code "59") (name "unconnected-(U3-3V-Pad2)") (class "Default")
      (node (ref "U3") (pin "2") (pinfunction "3V_2") (pintype "passive"))
    )
    (net (code "60") (name "unconnected-(U3-EOC-Pad6)") (class "Default")
      (node (ref "U3") (pin "6") (pinfunction "EOC_6") (pintype "passive+no_connect"))
    )
    (net (code "61") (name "unconnected-(U3-RST-Pad7)") (class "Default")
      (node (ref "U3") (pin "7") (pinfunction "RST_7") (pintype "passive+no_connect"))
    )
    (net (code "62") (name "unconnected-(U4-NC-Pad5)") (class "Default")
      (node (ref "U4") (pin "5") (pinfunction "NC_5") (pintype "passive+no_connect"))
    )
    (net (code "63") (name "unconnected-(U4-NC-Pad6)") (class "Default")
      (node (ref "U4") (pin "6") (pinfunction "NC_6") (pintype "passive+no_connect"))
    )
    (net (code "64") (name "unconnected-(U4-NC-Pad7)") (class "Default")
      (node (ref "U4") (pin "7") (pinfunction "NC_7") (pintype "passive+no_connect"))
    )
    (net (code "65") (name "unconnected-(U4-NC-Pad8)") (class "Default")
      (node (ref "U4") (pin "8") (pinfunction "NC_8") (pintype "passive+no_connect"))
    )
    (net (code "66") (name "unconnected-(U5-3VO-Pad2)") (class "Default")
      (node (ref "U5") (pin "2") (pinfunction "3VO_2") (pintype "passive+no_connect"))
    )
    (net (code "67") (name "unconnected-(U5-ADR-Pad8)") (class "Default")
      (node (ref "U5") (pin "8") (pinfunction "ADR_8") (pintype "passive+no_connect"))
    )
    (net (code "68") (name "unconnected-(U5-INT-Pad7)") (class "Default")
      (node (ref "U5") (pin "7") (pinfunction "INT_7") (pintype "passive+no_connect"))
    )
    (net (code "69") (name "unconnected-(U5-PS0-Pad9)") (class "Default")
      (node (ref "U5") (pin "9") (pinfunction "PS0_9") (pintype "power_in+no_connect"))
    )
    (net (code "70") (name "unconnected-(U5-PS1-Pad10)") (class "Default")
      (node (ref "U5") (pin "10") (pinfunction "PS1_10") (pintype "power_in+no_connect"))
    )
    (net (code "71") (name "unconnected-(U5-RST-Pad6)") (class "Default")
      (node (ref "U5") (pin "6") (pinfunction "RST_6") (pintype "passive+no_connect"))
    )
  )
)
